# blue.net
KiCad netlist of a schematic drawn in EAGLE
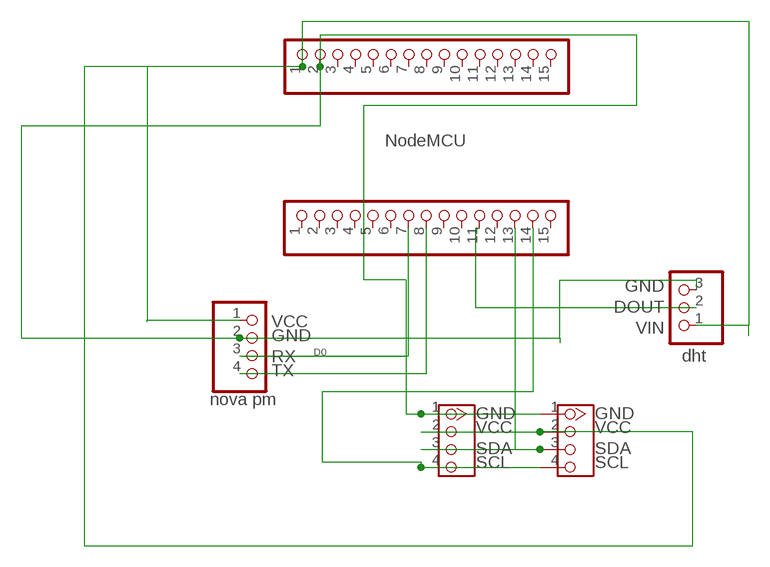
[diagram p0: schematic, sheet 1]

(export (version "E")
  (design (tool "Eeschema 10.0.6"))
  (components
    (comp (ref "J1")
      (value "4P-2.0")
      (footprint "eagle-import:HW4-2.0")
      (libsource (lib "eagle-import") (part "GROVE-CONNECTOR-DIP(4P-2.0)"))
    )
    (comp (ref "J2")
      (value "4P-2.0")
      (footprint "eagle-import:HW4-2.0")
      (libsource (lib "eagle-import") (part "GROVE-CONNECTOR-DIP(4P-2.0)"))
    )
    (comp (ref "JP1")
      (value "PINHD-1X15")
      (footprint "eagle-import:1X15")
      (libsource (lib "eagle-import") (part "PINHD-1X15"))
    )
    (comp (ref "JP2")
      (value "PINHD-1X15")
      (footprint "eagle-import:1X15")
      (libsource (lib "eagle-import") (part "PINHD-1X15"))
    )
    (comp (ref "JP3")
      (value "PINHD-1X3")
      (footprint "eagle-import:1X03")
      (libsource (lib "eagle-import") (part "PINHD-1X3"))
    )
    (comp (ref "JP4")
      (value "PINHD-1X4")
      (footprint "eagle-import:1X04")
      (libsource (lib "eagle-import") (part "PINHD-1X4"))
    )
  )
  (nets
    (net (code "1") (name "Net-(J1-Pad1)") (class "Default")
      (node (ref "J1") (pin "1") (pinfunction "1_1") (pintype "bidirectional"))
      (node (ref "J2") (pin "1") (pinfunction "1_1") (pintype "bidirectional"))
      (node (ref "JP2") (pin "2") (pinfunction "2_2") (pintype "passive"))
      (node (ref "JP3") (pin "3") (pinfunction "3_3") (pintype "passive"))
      (node (ref "JP4") (pin "2") (pinfunction "2_2") (pintype "passive"))
    )
    (net (code "2") (name "Net-(J1-Pad2)") (class "Default")
      (node (ref "J1") (pin "2") (pinfunction "2_2") (pintype "bidirectional"))
      (node (ref "J2") (pin "2") (pinfunction "2_2") (pintype "bidirectional"))
      (node (ref "JP2") (pin "1") (pinfunction "1_1") (pintype "passive"))
      (node (ref "JP3") (pin "1") (pinfunction "1_1") (pintype "passive"))
      (node (ref "JP4") (pin "1") (pinfunction "1_1") (pintype "passive"))
    )
    (net (code "3") (name "Net-(J1-Pad3)") (class "Default")
      (node (ref "J1") (pin "3") (pinfunction "3_3") (pintype "bidirectional"))
      (node (ref "J2") (pin "3") (pinfunction "3_3") (pintype "bidirectional"))
      (node (ref "JP1") (pin "13") (pinfunction "13_13") (pintype "passive"))
    )
    (net (code "4") (name "Net-(J1-Pad4)") (class "Default")
      (node (ref "J1") (pin "4") (pinfunction "4_4") (pintype "bidirectional"))
      (node (ref "J2") (pin "4") (pinfunction "4_4") (pintype "bidirectional"))
      (node (ref "JP1") (pin "14") (pinfunction "14_14") (pintype "passive"))
    )
    (net (code "5") (name "Net-(JP1-Pad7)") (class "Default")
      (node (ref "JP1") (pin "7") (pinfunction "7_7") (pintype "passive"))
      (node (ref "JP4") (pin "3") (pinfunction "3_3") (pintype "passive"))
    )
    (net (code "6") (name "Net-(JP1-Pad8)") (class "Default")
      (node (ref "JP1") (pin "8") (pinfunction "8_8") (pintype "passive"))
      (node (ref "JP4") (pin "4") (pinfunction "4_4") (pintype "passive"))
    )
    (net (code "7") (name "Net-(JP1-Pad11)") (class "Default")
      (node (ref "JP1") (pin "11") (pinfunction "11_11") (pintype "passive"))
      (node (ref "JP3") (pin "2") (pinfunction "2_2") (pintype "passive"))
    )
    (net (code "8") (name "unconnected-(JP1-Pad1)") (class "Default")
      (node (ref "JP1") (pin "1") (pinfunction "1_1") (pintype "passive"))
    )
    (net (code "9") (name "unconnected-(JP1-Pad2)") (class "Default")
      (node (ref "JP1") (pin "2") (pinfunction "2_2") (pintype "passive"))
    )
    (net (code "10") (name "unconnected-(JP1-Pad3)") (class "Default")
      (node (ref "JP1") (pin "3") (pinfunction "3_3") (pintype "passive"))
    )
    (net (code "11") (name "unconnected-(JP1-Pad4)") (class "Default")
      (node (ref "JP1") (pin "4") (pinfunction "4_4") (pintype "passive"))
    )
    (net (code "12") (name "unconnected-(JP1-Pad5)") (class "Default")
      (node (ref "JP1") (pin "5") (pinfunction "5_5") (pintype "passive"))
    )
    (net (code "13") (name "unconnected-(JP1-Pad6)") (class "Default")
      (node (ref "JP1") (pin "6") (pinfunction "6_6") (pintype "passive"))
    )
    (net (code "14") (name "unconnected-(JP1-Pad9)") (class "Default")
      (node (ref "JP1") (pin "9") (pinfunction "9_9") (pintype "passive"))
    )
    (net (code "15") (name "unconnected-(JP1-Pad10)") (class "Default")
      (node (ref "JP1") (pin "10") (pinfunction "10_10") (pintype "passive"))
    )
    (net (code "16") (name "unconnected-(JP1-Pad12)") (class "Default")
      (node (ref "JP1") (pin "12") (pinfunction "12_12") (pintype "passive"))
    )
    (net (code "17") (name "unconnected-(JP1-Pad15)") (class "Default")
      (node (ref "JP1") (pin "15") (pinfunction "15_15") (pintype "passive"))
    )
    (net (code "18") (name "unconnected-(JP2-Pad3)") (class "Default")
      (node (ref "JP2") (pin "3") (pinfunction "3_3") (pintype "passive"))
    )
    (net (code "19") (name "unconnected-(JP2-Pad4)") (class "Default")
      (node (ref "JP2") (pin "4") (pinfunction "4_4") (pintype "passive"))
    )
    (net (code "20") (name "unconnected-(JP2-Pad5)") (class "Default")
      (node (ref "JP2") (pin "5") (pinfunction "5_5") (pintype "passive"))
    )
    (net (code "21") (name "unconnected-(JP2-Pad6)") (class "Default")
      (node (ref "JP2") (pin "6") (pinfunction "6_6") (pintype "passive"))
    )
    (net (code "22") (name "unconnected-(JP2-Pad7)") (class "Default")
      (node (ref "JP2") (pin "7") (pinfunction "7_7") (pintype "passive"))
    )
    (net (code "23") (name "unconnected-(JP2-Pad8)") (class "Default")
      (node (ref "JP2") (pin "8") (pinfunction "8_8") (pintype "passive"))
    )
    (net (code "24") (name "unconnected-(JP2-Pad9)") (class "Default")
      (node (ref "JP2") (pin "9") (pinfunction "9_9") (pintype "passive"))
    )
    (net (code "25") (name "unconnected-(JP2-Pad10)") (class "Default")
      (node (ref "JP2") (pin "10") (pinfunction "10_10") (pintype "passive"))
    )
    (net (code "26") (name "unconnected-(JP2-Pad11)") (class "Default")
      (node (ref "JP2") (pin "11") (pinfunction "11_11") (pintype "passive"))
    )
    (net (code "27") (name "unconnected-(JP2-Pad12)") (class "Default")
      (node (ref "JP2") (pin "12") (pinfunction "12_12") (pintype "passive"))
    )
    (net (code "28") (name "unconnected-(JP2-Pad13)") (class "Default")
      (node (ref "JP2") (pin "13") (pinfunction "13_13") (pintype "passive"))
    )
    (net (code "29") (name "unconnected-(JP2-Pad14)") (class "Default")
      (node (ref "JP2") (pin "14") (pinfunction "14_14") (pintype "passive"))
    )
    (net (code "30") (name "unconnected-(JP2-Pad15)") (class "Default")
      (node (ref "JP2") (pin "15") (pinfunction "15_15") (pintype "passive"))
    )
  )
)
